# SCH_M5_Stick_RedHat_Shield_2022-06-05.net
KiCad netlist of a schematic drawn in EasyEDA
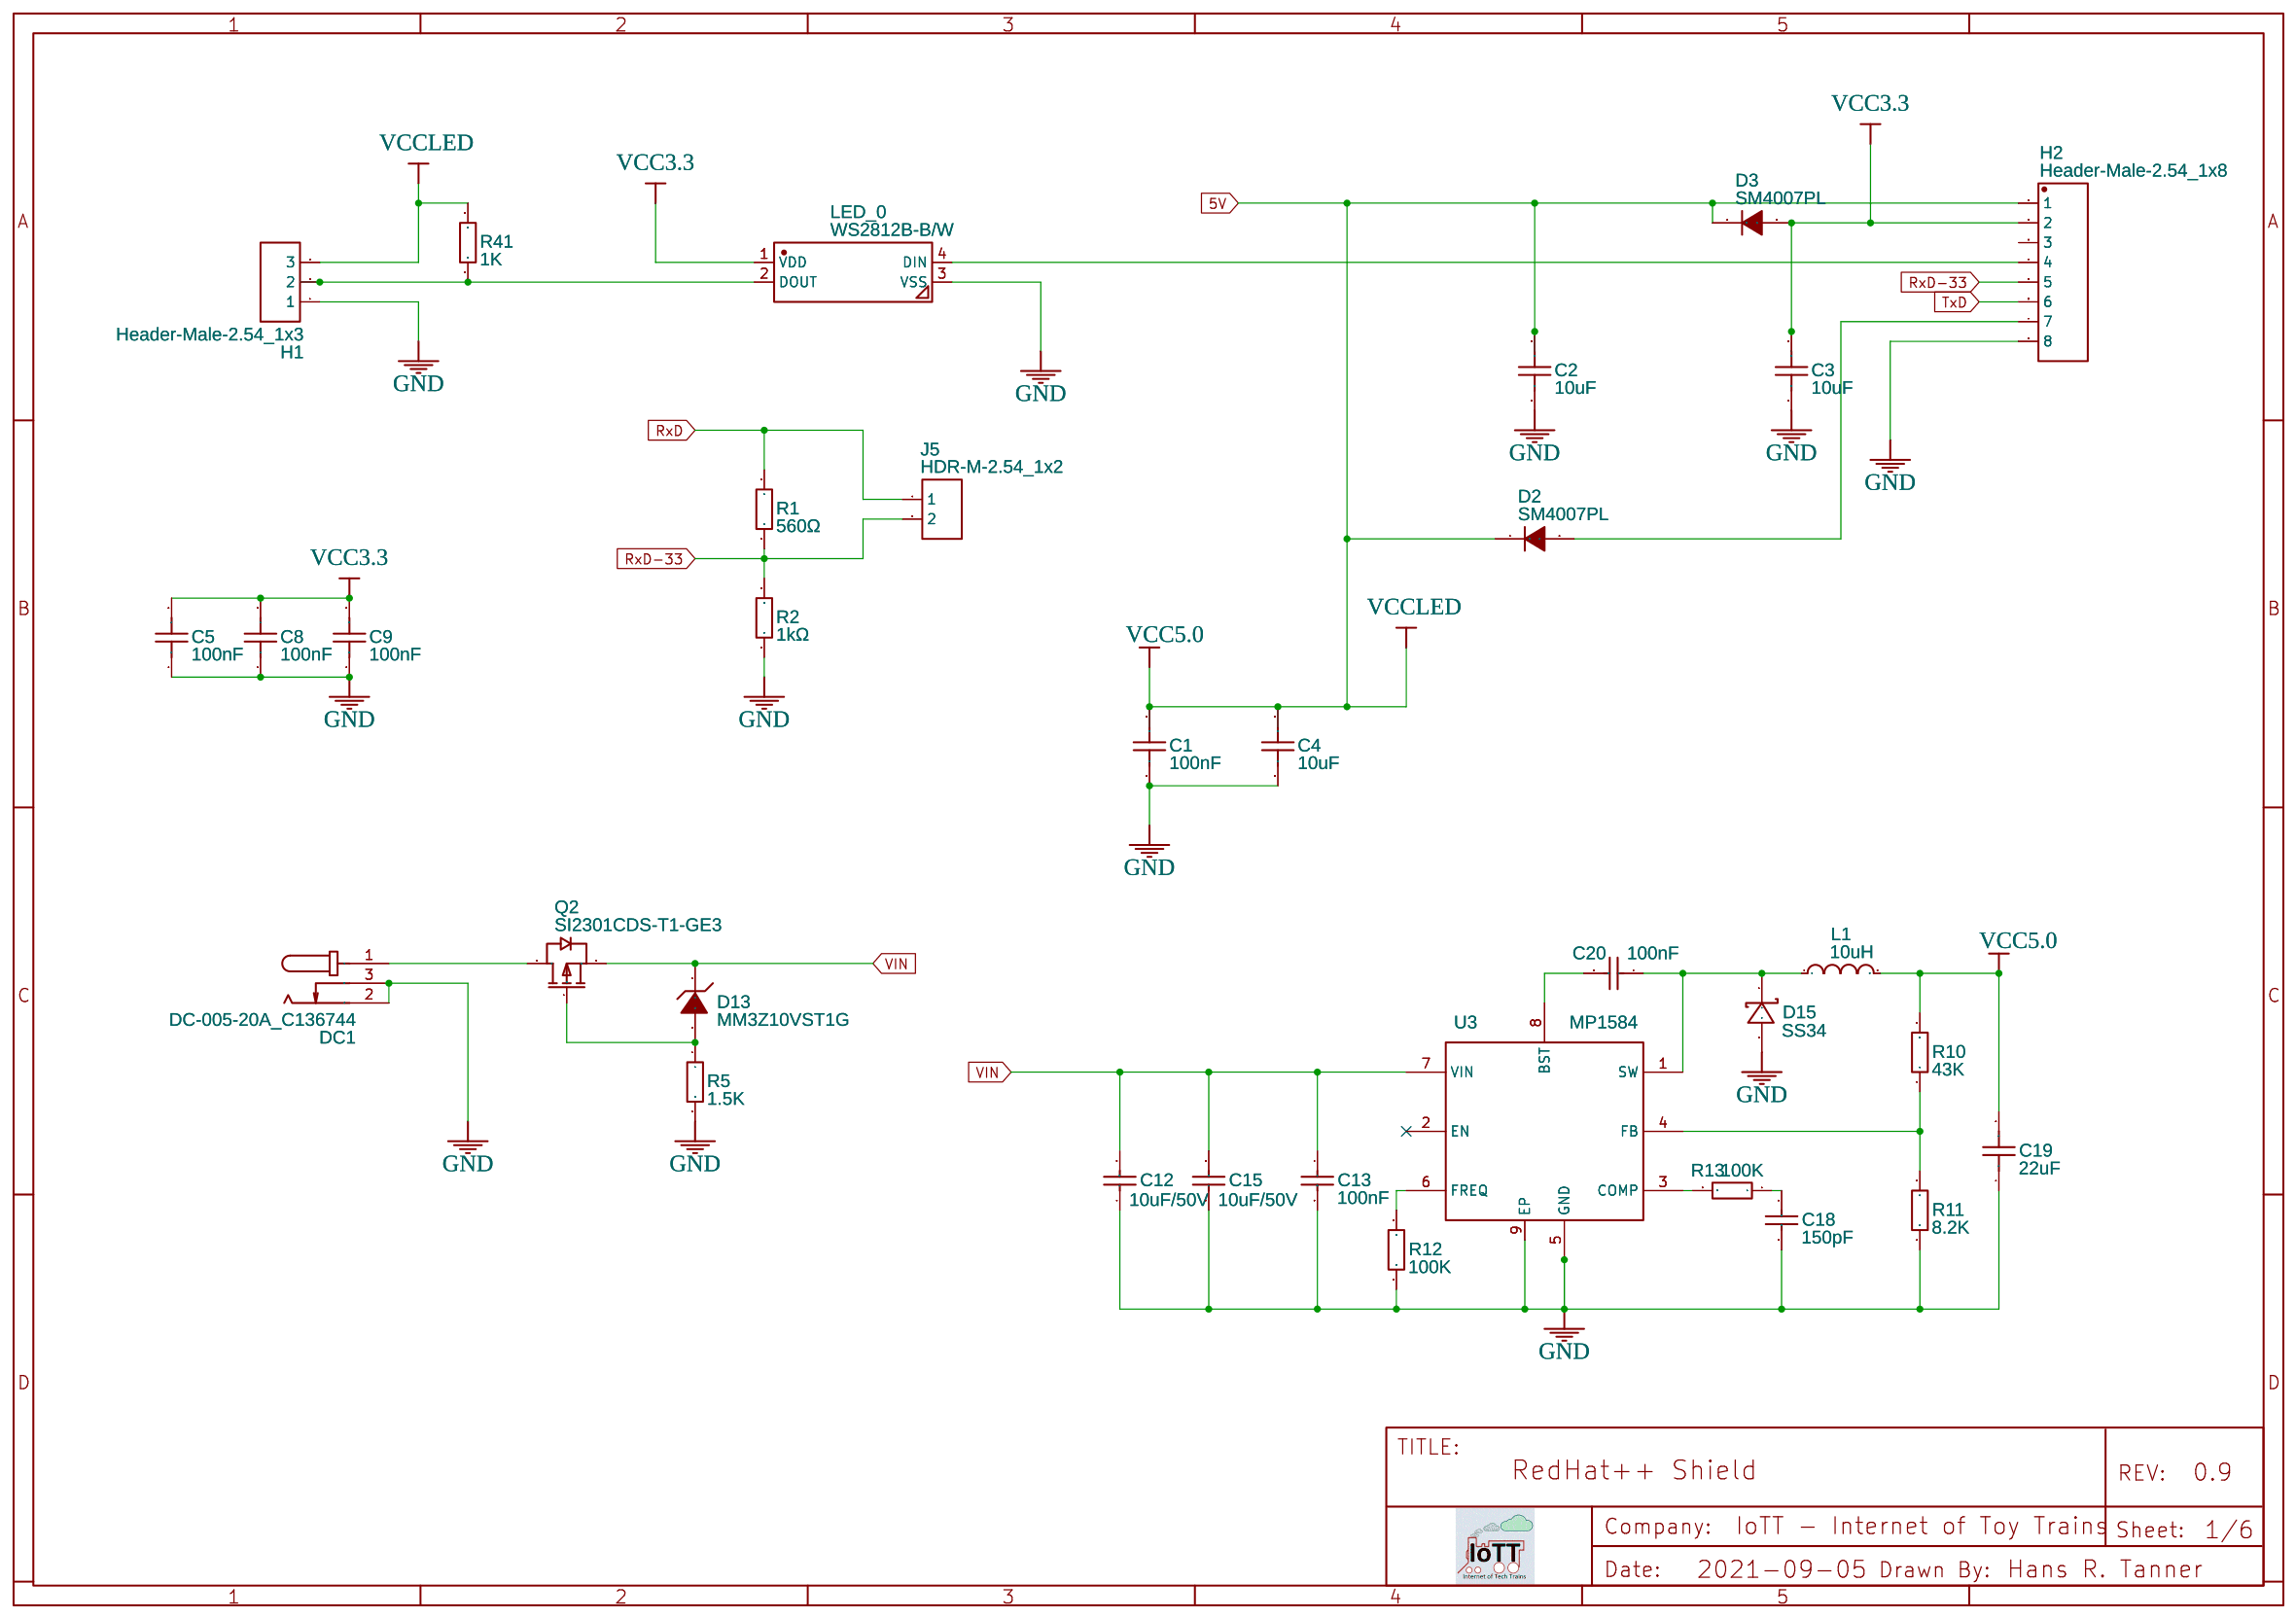
[diagram p0: RedHat++ Shield Main]
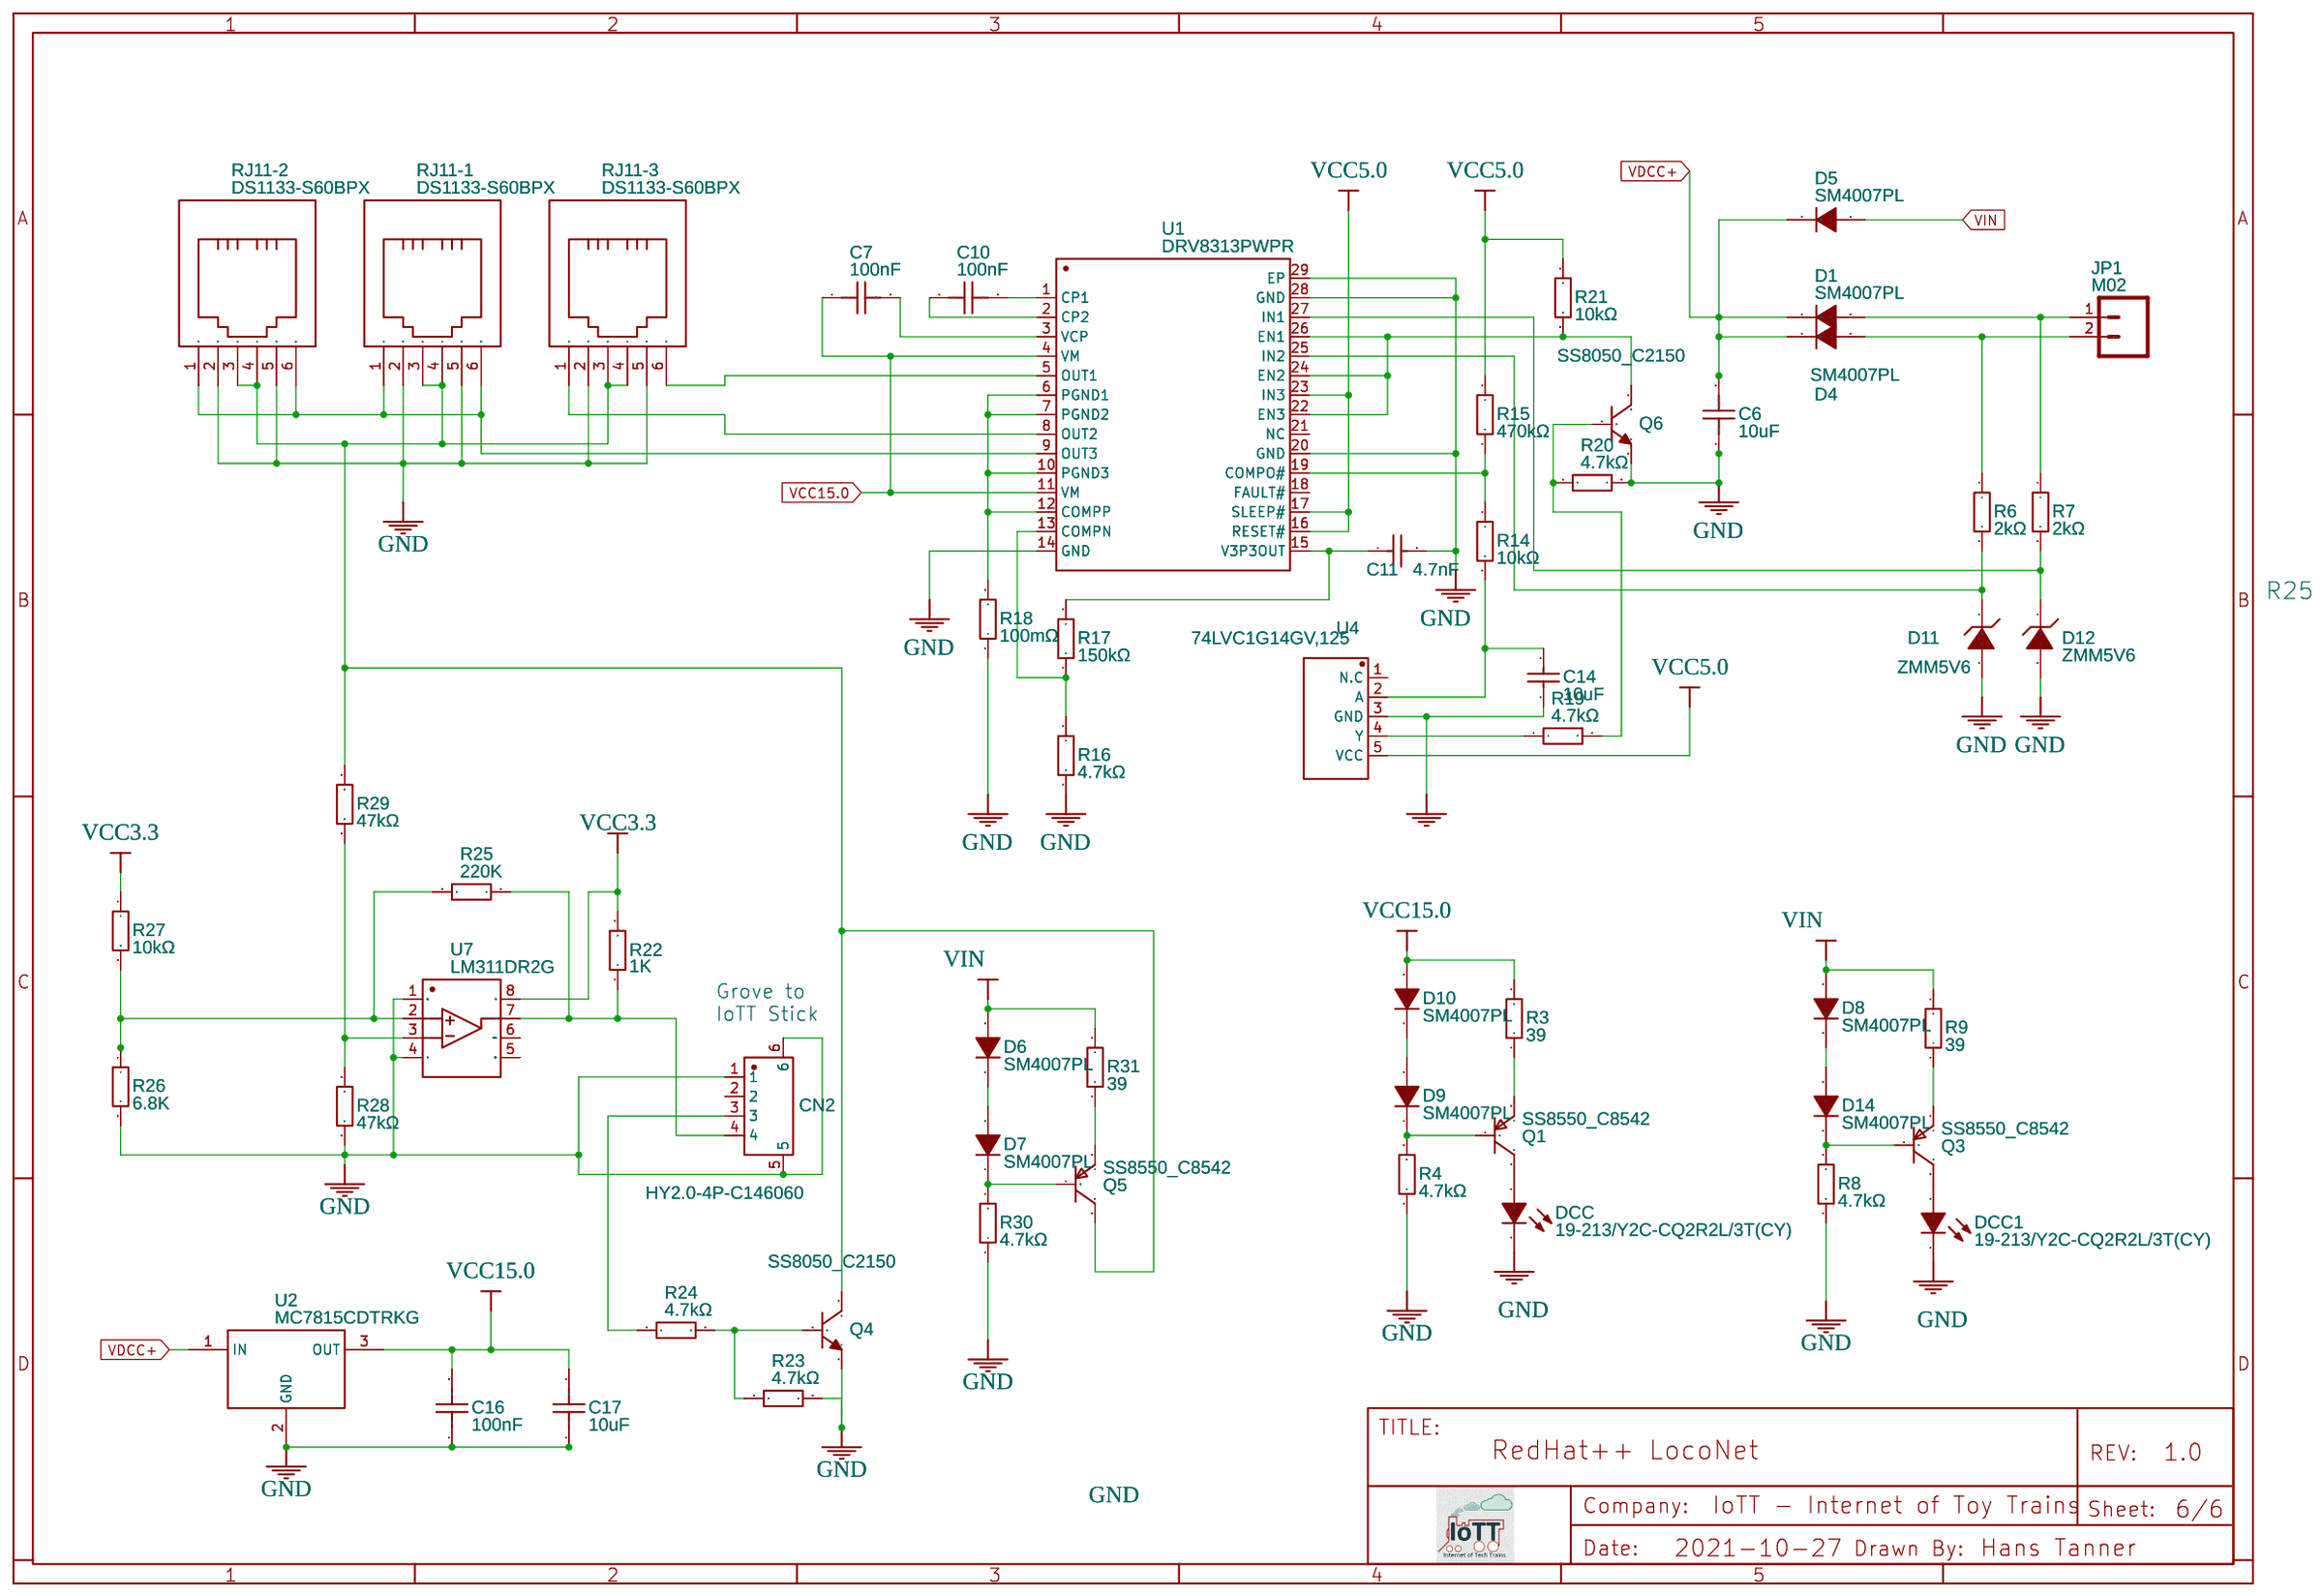
[diagram p1: LocoNet]
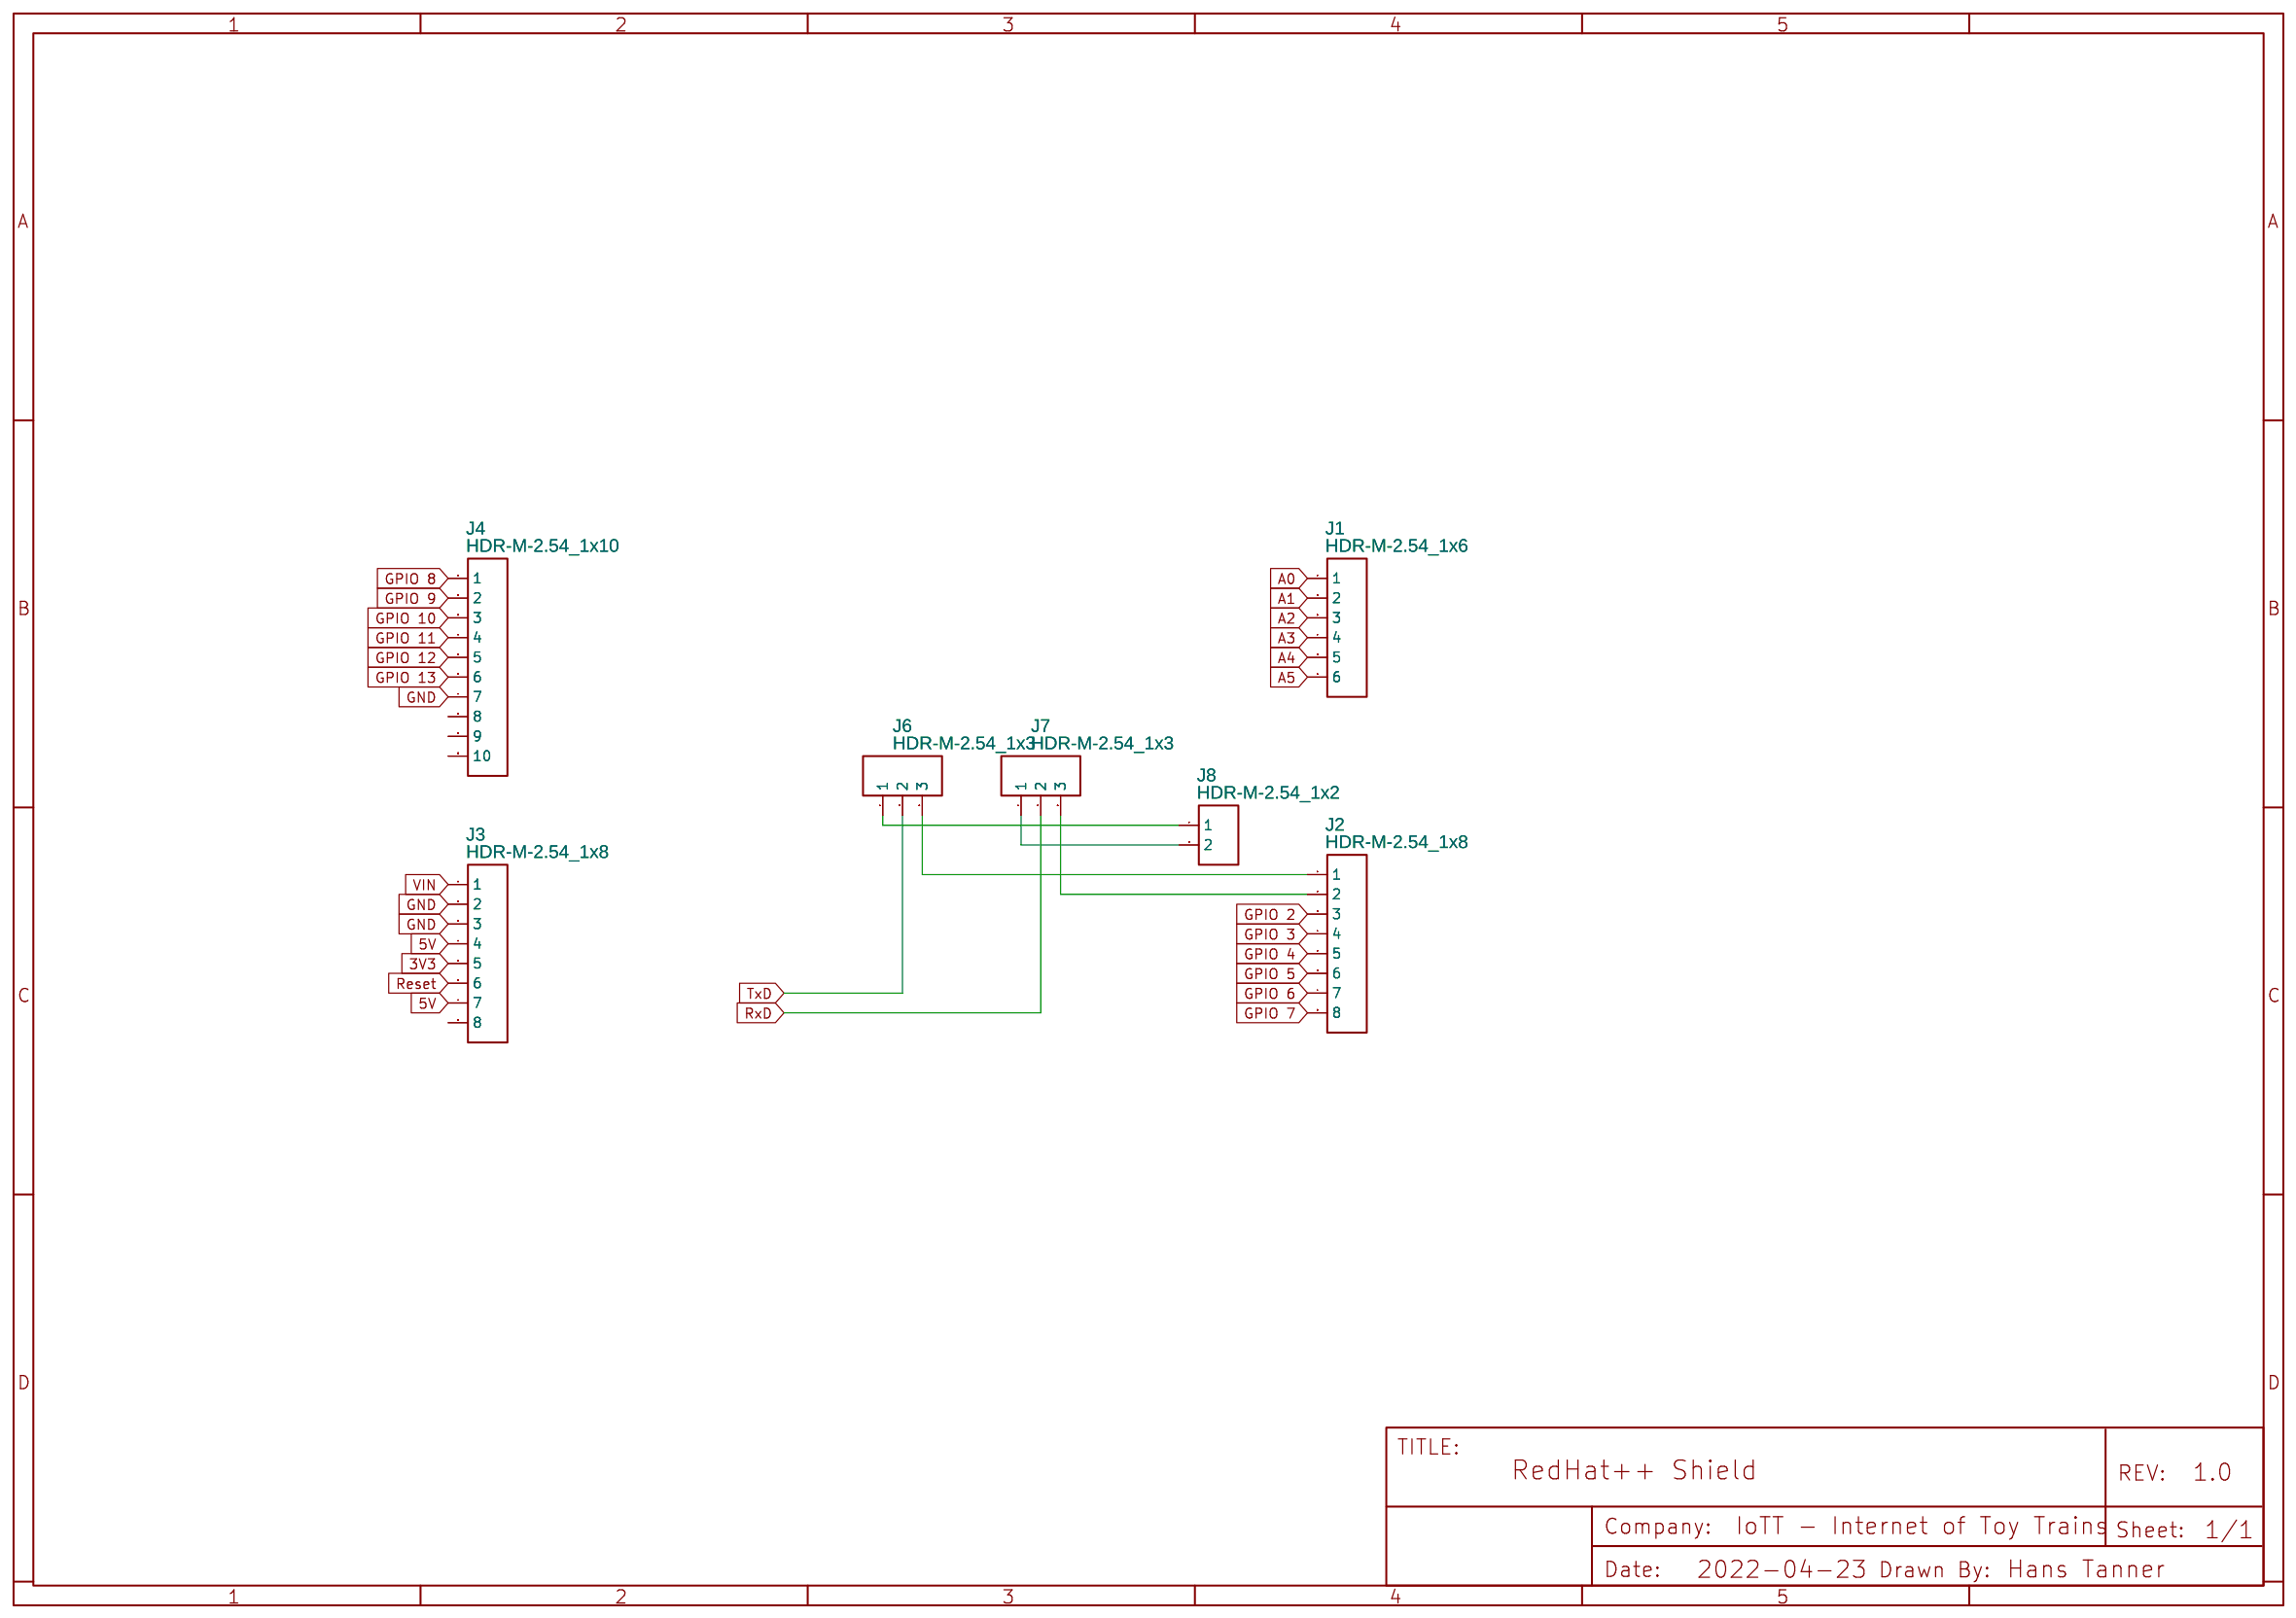
[diagram p2: Arduino Headers]

(export (version "E")
  (design (tool "Eeschema 10.0.6"))
  (components
    (comp (ref "C1")
      (value "100nF")
      (fields
        (field (name "BOM_Manufacturer Part") "CC0603KRX7R9BB104")
        (field (name "BOM_Supplier Part") "C14663")
      )
      (libsource (lib "") (part "CC0603KRX7R9BB104"))
    )
    (comp (ref "C2")
      (value "10uF")
      (fields
        (field (name "BOM_Manufacturer Part") "GRM21BR61H106KE43L")
        (field (name "BOM_Supplier Part") "C440198")
      )
      (libsource (lib "") (part "GRM21BR61H106KE43L"))
    )
    (comp (ref "C3")
      (value "10uF")
      (fields
        (field (name "BOM_Manufacturer Part") "GRM21BR61H106KE43L")
        (field (name "BOM_Supplier Part") "C440198")
      )
      (libsource (lib "") (part "GRM21BR61H106KE43L"))
    )
    (comp (ref "C4")
      (value "10uF")
      (fields
        (field (name "BOM_Manufacturer Part") "GRM21BR61H106KE43L")
        (field (name "BOM_Supplier Part") "C440198")
      )
      (libsource (lib "") (part "GRM21BR61H106KE43L"))
    )
    (comp (ref "C5")
      (value "100nF")
      (fields
        (field (name "BOM_Manufacturer Part") "CC0603KRX7R9BB104")
        (field (name "BOM_Supplier Part") "C14663")
      )
      (libsource (lib "") (part "CC0603KRX7R9BB104"))
    )
    (comp (ref "C8")
      (value "100nF")
      (fields
        (field (name "BOM_Manufacturer Part") "CC0603KRX7R9BB104")
        (field (name "BOM_Supplier Part") "C14663")
      )
      (libsource (lib "") (part "CC0603KRX7R9BB104"))
    )
    (comp (ref "C9")
      (value "100nF")
      (fields
        (field (name "BOM_Manufacturer Part") "CC0603KRX7R9BB104")
        (field (name "BOM_Supplier Part") "C14663")
      )
      (libsource (lib "") (part "CC0603KRX7R9BB104"))
    )
    (comp (ref "C12")
      (value "10uF/50V")
      (fields
        (field (name "BOM_Manufacturer Part") "CL31A106KBHNNNE")
        (field (name "BOM_Supplier Part") "C13585")
      )
      (libsource (lib "") (part "CL31A106KBHNNNE"))
    )
    (comp (ref "C13")
      (value "100nF")
      (fields
        (field (name "BOM_Manufacturer Part") "CL31B104KBCNNNC")
        (field (name "BOM_Supplier Part") "C24497")
      )
      (libsource (lib "") (part "CL31B104KBCNNNC_1"))
    )
    (comp (ref "C15")
      (value "10uF/50V")
      (fields
        (field (name "BOM_Manufacturer Part") "CL31A106KBHNNNE")
        (field (name "BOM_Supplier Part") "C13585")
      )
      (libsource (lib "") (part "CL31A106KBHNNNE"))
    )
    (comp (ref "C18")
      (value "150pF")
      (fields
        (field (name "BOM_Manufacturer Part") "0805B151K500NT")
        (field (name "BOM_Supplier Part") "C1716")
      )
      (libsource (lib "") (part "0805B151K500NT"))
    )
    (comp (ref "C19")
      (value "22uF")
      (fields
        (field (name "BOM_Manufacturer Part") "CL21A226MAQNNNE")
        (field (name "BOM_Supplier Part") "C45783")
      )
      (libsource (lib "") (part "CL21A226MAQNNNE"))
    )
    (comp (ref "C20")
      (value "100nF")
      (fields
        (field (name "BOM_Manufacturer Part") "CL31B104KBCNNNC")
        (field (name "BOM_Supplier Part") "C24497")
      )
      (libsource (lib "") (part "CL31B104KBCNNNC"))
    )
    (comp (ref "D2")
      (value "SM4007PL")
      (fields (field (name "BOM_Supplier Part") "C64898"))
      (libsource (lib "") (part "SM4007PL"))
    )
    (comp (ref "D3")
      (value "SM4007PL")
      (fields (field (name "BOM_Supplier Part") "C64898"))
      (libsource (lib "") (part "SM4007PL"))
    )
    (comp (ref "D13")
      (value "MM3Z10VST1G")
      (fields (field (name "BOM_Supplier Part") "C235983"))
      (libsource (lib "") (part "MM3Z10VST1G"))
    )
    (comp (ref "D15")
      (value "SS34")
      (fields (field (name "BOM_Supplier Part") "C8678"))
      (libsource (lib "") (part "SS34_C8678"))
    )
    (comp (ref "DC1")
      (value "DC-005-20A_C136744")
      (fields
        (field (name "BOM_Manufacturer Part") "DC-005-20A")
        (field (name "BOM_Supplier Part") "C136744")
      )
      (libsource (lib "") (part "DC-005-20A_C136744"))
    )
    (comp (ref "H1")
      (value "Header-Male-2.54_1x3")
      (fields
        (field (name "BOM_Manufacturer Part") "Header2.54mm 1*3P")
        (field (name "BOM_Supplier Part") "C49257")
      )
      (libsource (lib "") (part "Header-Male-2.54_1x3"))
    )
    (comp (ref "H2")
      (value "Header-Male-2.54_1x8")
      (fields
        (field (name "BOM_Manufacturer Part") "210S-1*8P L=11.6MMGold-plated black")
        (field (name "BOM_Supplier Part") "C124381")
      )
      (libsource (lib "") (part "Header-Male-2.54_1x8"))
    )
    (comp (ref "J5")
      (value "HDR-M-2.54_1x2")
      (fields (field (name "BOM_Supplier Part") "C124375"))
      (libsource (lib "") (part "HDR-M-2.54_1x2"))
    )
    (comp (ref "L1")
      (value "10uH")
      (fields
        (field (name "BOM_Manufacturer Part") "MWSA0603-100MT")
        (field (name "BOM_Supplier Part") "C132141")
      )
      (libsource (lib "") (part "MWSA0603-100MT"))
    )
    (comp (ref "LED_0")
      (value "WS2812B-B/W")
      (fields (field (name "BOM_Supplier Part") "C2761795"))
      (libsource (lib "") (part "WS2812B-B/W"))
    )
    (comp (ref "Q2")
      (value "SI2301CDS-T1-GE3")
      (fields (field (name "BOM_Supplier Part") "C10487"))
      (libsource (lib "") (part "SI2301CDS-T1-GE3"))
    )
    (comp (ref "R1")
      (value "560Ω")
      (fields
        (field (name "BOM_Manufacturer Part") "0603WAF5600T5E")
        (field (name "BOM_Supplier Part") "C23204")
      )
      (libsource (lib "") (part "0603WAF5600T5E"))
    )
    (comp (ref "R2")
      (value "1kΩ")
      (fields
        (field (name "BOM_Manufacturer Part") "0402WGF1001TCE")
        (field (name "BOM_Supplier Part") "C11702")
      )
      (libsource (lib "") (part "0402WGF1001TCE"))
    )
    (comp (ref "R5")
      (value "1.5K")
      (fields
        (field (name "BOM_Manufacturer Part") "0402WGF1501TCE")
        (field (name "BOM_Supplier Part") "C25867")
      )
      (libsource (lib "") (part "0402WGF1501TCE"))
    )
    (comp (ref "R10")
      (value "43K")
      (fields
        (field (name "BOM_Manufacturer Part") "0805W8F4302T5E")
        (field (name "BOM_Supplier Part") "C17695")
      )
      (libsource (lib "") (part "0805W8F4302T5E"))
    )
    (comp (ref "R11")
      (value "8.2K")
      (fields
        (field (name "BOM_Manufacturer Part") "0805W8F8201T5E")
        (field (name "BOM_Supplier Part") "C17828")
      )
      (libsource (lib "") (part "0805W8F8201T5E"))
    )
    (comp (ref "R12")
      (value "100K")
      (fields
        (field (name "BOM_Manufacturer Part") "0805W8F1003T5E")
        (field (name "BOM_Supplier Part") "C17407")
      )
      (libsource (lib "") (part "0805W8F1003T5E_1"))
    )
    (comp (ref "R13")
      (value "100K")
      (fields
        (field (name "BOM_Manufacturer Part") "0805W8F1003T5E")
        (field (name "BOM_Supplier Part") "C17407")
      )
      (libsource (lib "") (part "0805W8F1003T5E"))
    )
    (comp (ref "R41")
      (value "1K")
      (fields
        (field (name "BOM_Manufacturer Part") "0402WGF1001TCE")
        (field (name "BOM_Supplier Part") "C11702")
      )
      (libsource (lib "") (part "0402WGF1001TCE"))
    )
    (comp (ref "U3")
      (value "MP1584")
      (fields
        (field (name "BOM_Manufacturer Part") "MP1584EN-LF-Z")
        (field (name "BOM_Supplier Part") "C15051")
      )
      (libsource (lib "") (part "MP1584EN-LF-Z"))
    )
    (comp (ref "C6")
      (value "10uF")
      (fields
        (field (name "BOM_Manufacturer Part") "GRM21BR61H106KE43L")
        (field (name "BOM_Supplier Part") "C440198")
      )
      (libsource (lib "") (part "GRM21BR61H106KE43L"))
    )
    (comp (ref "C7")
      (value "100nF")
      (fields
        (field (name "BOM_Manufacturer Part") "CC0603KRX7R9BB104")
        (field (name "BOM_Supplier Part") "C14663")
      )
      (libsource (lib "") (part "CC0603KRX7R9BB104_1"))
    )
    (comp (ref "C10")
      (value "100nF")
      (fields
        (field (name "BOM_Manufacturer Part") "CC0603KRX7R9BB104")
        (field (name "BOM_Supplier Part") "C14663")
      )
      (libsource (lib "") (part "CC0603KRX7R9BB104_1"))
    )
    (comp (ref "C11")
      (value "4.7nF")
      (fields
        (field (name "BOM_Manufacturer Part") "0402B472K500NT")
        (field (name "BOM_Supplier Part") "C1538")
      )
      (libsource (lib "") (part "0402B472K500NT"))
    )
    (comp (ref "C14")
      (value "10uF")
      (fields
        (field (name "BOM_Manufacturer Part") "CL21A106KAYNNNE")
        (field (name "BOM_Supplier Part") "C15850")
      )
      (libsource (lib "") (part "CL21A106KAYNNNE"))
    )
    (comp (ref "C16")
      (value "100nF")
      (fields
        (field (name "BOM_Manufacturer Part") "CC0603KRX7R9BB104")
        (field (name "BOM_Supplier Part") "C14663")
      )
      (libsource (lib "") (part "CC0603KRX7R9BB104"))
    )
    (comp (ref "C17")
      (value "10uF")
      (fields
        (field (name "BOM_Manufacturer Part") "GRM21BR61H106KE43L")
        (field (name "BOM_Supplier Part") "C440198")
      )
      (libsource (lib "") (part "GRM21BR61H106KE43L"))
    )
    (comp (ref "CN2")
      (value "HY2.0-4P-C146060")
      (fields (field (name "BOM_Supplier Part") "C146060"))
      (libsource (lib "") (part "HY2.0-4P-C146060"))
    )
    (comp (ref "D1")
      (value "SM4007PL")
      (fields (field (name "BOM_Supplier Part") "C64898"))
      (libsource (lib "") (part "SM4007PL_1"))
    )
    (comp (ref "D4")
      (value "SM4007PL")
      (fields (field (name "BOM_Supplier Part") "C64898"))
      (libsource (lib "") (part "SM4007PL_1"))
    )
    (comp (ref "D5")
      (value "SM4007PL")
      (fields (field (name "BOM_Supplier Part") "C64898"))
      (libsource (lib "") (part "SM4007PL_1"))
    )
    (comp (ref "D6")
      (value "SM4007PL")
      (fields (field (name "BOM_Supplier Part") "C64898"))
      (libsource (lib "") (part "SM4007PL"))
    )
    (comp (ref "D7")
      (value "SM4007PL")
      (fields (field (name "BOM_Supplier Part") "C64898"))
      (libsource (lib "") (part "SM4007PL"))
    )
    (comp (ref "D8")
      (value "SM4007PL")
      (fields (field (name "BOM_Supplier Part") "C64898"))
      (libsource (lib "") (part "SM4007PL"))
    )
    (comp (ref "D9")
      (value "SM4007PL")
      (fields (field (name "BOM_Supplier Part") "C64898"))
      (libsource (lib "") (part "SM4007PL"))
    )
    (comp (ref "D10")
      (value "SM4007PL")
      (fields (field (name "BOM_Supplier Part") "C64898"))
      (libsource (lib "") (part "SM4007PL"))
    )
    (comp (ref "D11")
      (value "ZMM5V6")
      (fields (field (name "BOM_Supplier Part") "C8062"))
      (libsource (lib "") (part "ZMM5V6"))
    )
    (comp (ref "D12")
      (value "ZMM5V6")
      (fields (field (name "BOM_Supplier Part") "C8062"))
      (libsource (lib "") (part "ZMM5V6"))
    )
    (comp (ref "D14")
      (value "SM4007PL")
      (fields (field (name "BOM_Supplier Part") "C64898"))
      (libsource (lib "") (part "SM4007PL"))
    )
    (comp (ref "DCC")
      (value "19-213/Y2C-CQ2R2L/3T(CY)")
      (fields (field (name "BOM_Supplier Part") "C72038"))
      (libsource (lib "") (part "19-213/Y2C-CQ2R2L/3T(CY)"))
    )
    (comp (ref "DCC1")
      (value "19-213/Y2C-CQ2R2L/3T(CY)")
      (fields (field (name "BOM_Supplier Part") "C72038"))
      (libsource (lib "") (part "19-213/Y2C-CQ2R2L/3T(CY)"))
    )
    (comp (ref "JP1") (value "M02") (libsource (lib "") (part "M02")))
    (comp (ref "Q1")
      (value "SS8550_C8542")
      (fields (field (name "BOM_Manufacturer Part") "SS8550") (field (name "BOM_Supplier Part") "C8542"))
      (libsource (lib "") (part "SS8550_C8542"))
    )
    (comp (ref "Q3")
      (value "SS8550_C8542")
      (fields (field (name "BOM_Manufacturer Part") "SS8550") (field (name "BOM_Supplier Part") "C8542"))
      (libsource (lib "") (part "SS8550_C8542"))
    )
    (comp (ref "Q4")
      (value "SS8050_C2150")
      (fields (field (name "BOM_Manufacturer Part") "SS8050") (field (name "BOM_Supplier Part") "C2150"))
      (libsource (lib "") (part "SS8050_C2150"))
    )
    (comp (ref "Q5")
      (value "SS8550_C8542")
      (fields (field (name "BOM_Manufacturer Part") "SS8550") (field (name "BOM_Supplier Part") "C8542"))
      (libsource (lib "") (part "SS8550_C8542"))
    )
    (comp (ref "Q6")
      (value "SS8050_C2150")
      (fields (field (name "BOM_Manufacturer Part") "SS8050") (field (name "BOM_Supplier Part") "C2150"))
      (libsource (lib "") (part "SS8050_C2150"))
    )
    (comp (ref "R3")
      (value "39")
      (fields
        (field (name "BOM_Manufacturer Part") "TC0325B390JT5E")
        (field (name "BOM_Supplier Part") "C146566")
      )
      (libsource (lib "") (part "TC0325B390JT5E"))
    )
    (comp (ref "R4")
      (value "4.7kΩ")
      (fields
        (field (name "BOM_Manufacturer Part") "0402WGF4701TCE")
        (field (name "BOM_Supplier Part") "C25900")
      )
      (libsource (lib "") (part "0402WGF4701TCE"))
    )
    (comp (ref "R6")
      (value "2kΩ")
      (fields
        (field (name "BOM_Manufacturer Part") "0402WGF2001TCE")
        (field (name "BOM_Supplier Part") "C4109")
      )
      (libsource (lib "") (part "0402WGF2001TCE"))
    )
    (comp (ref "R7")
      (value "2kΩ")
      (fields
        (field (name "BOM_Manufacturer Part") "0402WGF2001TCE")
        (field (name "BOM_Supplier Part") "C4109")
      )
      (libsource (lib "") (part "0402WGF2001TCE"))
    )
    (comp (ref "R8")
      (value "4.7kΩ")
      (fields
        (field (name "BOM_Manufacturer Part") "0402WGF4701TCE")
        (field (name "BOM_Supplier Part") "C25900")
      )
      (libsource (lib "") (part "0402WGF4701TCE"))
    )
    (comp (ref "R9")
      (value "39")
      (fields
        (field (name "BOM_Manufacturer Part") "TC0325B390JT5E")
        (field (name "BOM_Supplier Part") "C146566")
      )
      (libsource (lib "") (part "TC0325B390JT5E"))
    )
    (comp (ref "R14")
      (value "10kΩ")
      (fields
        (field (name "BOM_Manufacturer Part") "0402WGF1002TCE")
        (field (name "BOM_Supplier Part") "C25744")
      )
      (libsource (lib "") (part "0402WGF1002TCE"))
    )
    (comp (ref "R15")
      (value "470kΩ")
      (fields
        (field (name "BOM_Manufacturer Part") "0603WAF4703T5E")
        (field (name "BOM_Supplier Part") "C23178")
      )
      (libsource (lib "") (part "0603WAF4703T5E"))
    )
    (comp (ref "R16")
      (value "4.7kΩ")
      (fields
        (field (name "BOM_Manufacturer Part") "0402WGF4701TCE")
        (field (name "BOM_Supplier Part") "C25900")
      )
      (libsource (lib "") (part "0402WGF4701TCE"))
    )
    (comp (ref "R17")
      (value "150kΩ")
      (fields
        (field (name "BOM_Manufacturer Part") "0603WAF1503T5E")
        (field (name "BOM_Supplier Part") "C22807")
      )
      (libsource (lib "") (part "0603WAF1503T5E"))
    )
    (comp (ref "R18")
      (value "100mΩ")
      (fields
        (field (name "BOM_Manufacturer Part") "1206W4F100LT5E")
        (field (name "BOM_Supplier Part") "C25334")
      )
      (libsource (lib "") (part "1206W4F100LT5E"))
    )
    (comp (ref "R19")
      (value "4.7kΩ")
      (fields
        (field (name "BOM_Manufacturer Part") "0402WGF4701TCE")
        (field (name "BOM_Supplier Part") "C25900")
      )
      (libsource (lib "") (part "0402WGF4701TCE_1"))
    )
    (comp (ref "R20")
      (value "4.7kΩ")
      (fields
        (field (name "BOM_Manufacturer Part") "0402WGF4701TCE")
        (field (name "BOM_Supplier Part") "C25900")
      )
      (libsource (lib "") (part "0402WGF4701TCE_1"))
    )
    (comp (ref "R21")
      (value "10kΩ")
      (fields
        (field (name "BOM_Manufacturer Part") "0402WGF1002TCE")
        (field (name "BOM_Supplier Part") "C25744")
      )
      (libsource (lib "") (part "0402WGF1002TCE"))
    )
    (comp (ref "R22")
      (value "1K")
      (fields
        (field (name "BOM_Manufacturer Part") "0402WGF1001TCE")
        (field (name "BOM_Supplier Part") "C11702")
      )
      (libsource (lib "") (part "0402WGF1001TCE"))
    )
    (comp (ref "R23")
      (value "4.7kΩ")
      (fields
        (field (name "BOM_Manufacturer Part") "0402WGF4701TCE")
        (field (name "BOM_Supplier Part") "C25900")
      )
      (libsource (lib "") (part "0402WGF4701TCE_1"))
    )
    (comp (ref "R24")
      (value "4.7kΩ")
      (fields
        (field (name "BOM_Manufacturer Part") "0402WGF4701TCE")
        (field (name "BOM_Supplier Part") "C25900")
      )
      (libsource (lib "") (part "0402WGF4701TCE_1"))
    )
    (comp (ref "R25")
      (value "220K")
      (fields
        (field (name "BOM_Manufacturer Part") "0603WAF2203T5E")
        (field (name "BOM_Supplier Part") "C22961")
      )
      (libsource (lib "") (part "0603WAF2203T5E"))
    )
    (comp (ref "R26")
      (value "6.8K")
      (fields
        (field (name "BOM_Manufacturer Part") "0603WAF6801T5E")
        (field (name "BOM_Supplier Part") "C23212")
      )
      (libsource (lib "") (part "0603WAF6801T5E"))
    )
    (comp (ref "R27")
      (value "10kΩ")
      (fields
        (field (name "BOM_Manufacturer Part") "0402WGF1002TCE")
        (field (name "BOM_Supplier Part") "C25744")
      )
      (libsource (lib "") (part "0402WGF1002TCE"))
    )
    (comp (ref "R28")
      (value "47kΩ")
      (fields
        (field (name "BOM_Manufacturer Part") "0402WGF4702TCE")
        (field (name "BOM_Supplier Part") "C25792")
      )
      (libsource (lib "") (part "0402WGF4702TCE"))
    )
    (comp (ref "R29")
      (value "47kΩ")
      (fields
        (field (name "BOM_Manufacturer Part") "0402WGF4702TCE")
        (field (name "BOM_Supplier Part") "C25792")
      )
      (libsource (lib "") (part "0402WGF4702TCE"))
    )
    (comp (ref "R30")
      (value "4.7kΩ")
      (fields
        (field (name "BOM_Manufacturer Part") "0402WGF4701TCE")
        (field (name "BOM_Supplier Part") "C25900")
      )
      (libsource (lib "") (part "0402WGF4701TCE"))
    )
    (comp (ref "R31")
      (value "39")
      (fields
        (field (name "BOM_Manufacturer Part") "TC0325B390JT5E")
        (field (name "BOM_Supplier Part") "C146566")
      )
      (libsource (lib "") (part "TC0325B390JT5E"))
    )
    (comp (ref "RJ11-1")
      (value "DS1133-S60BPX")
      (fields (field (name "BOM_Supplier Part") "C77859"))
      (libsource (lib "") (part "Unknown_215_-660"))
    )
    (comp (ref "RJ11-2")
      (value "DS1133-S60BPX")
      (fields (field (name "BOM_Supplier Part") "C77859"))
      (libsource (lib "") (part "Unknown_120_-660"))
    )
    (comp (ref "RJ11-3")
      (value "DS1133-S60BPX")
      (fields (field (name "BOM_Supplier Part") "C77859"))
      (libsource (lib "") (part "Unknown_310_-660"))
    )
    (comp (ref "U1")
      (value "DRV8313PWPR")
      (fields (field (name "BOM_Supplier Part") "C92482"))
      (libsource (lib "") (part "DRV8313PWPR"))
    )
    (comp (ref "U2")
      (value "MC7815CDTRKG")
      (fields (field (name "BOM_Supplier Part") "C133887"))
      (libsource (lib "") (part "MC7815CDTRKG"))
    )
    (comp (ref "U4")
      (value "74LVC1G14GV,125")
      (fields (field (name "BOM_Supplier Part") "C131093"))
      (libsource (lib "") (part "74LVC1G14GV,125"))
    )
    (comp (ref "U7")
      (value "LM311DR2G")
      (fields (field (name "BOM_Supplier Part") "C231850"))
      (libsource (lib "") (part "LM311DR2G"))
    )
    (comp (ref "J1")
      (value "HDR-M-2.54_1x6")
      (fields (field (name "BOM_Supplier Part") "C190819"))
      (libsource (lib "") (part "HDR-M-2.54_1x6"))
    )
    (comp (ref "J2")
      (value "HDR-M-2.54_1x8")
      (fields (field (name "BOM_Supplier Part") "C190820"))
      (libsource (lib "") (part "HDR-M-2.54_1x8"))
    )
    (comp (ref "J3")
      (value "HDR-M-2.54_1x8")
      (fields (field (name "BOM_Supplier Part") "C190820"))
      (libsource (lib "") (part "HDR-M-2.54_1x8"))
    )
    (comp (ref "J4")
      (value "HDR-M-2.54_1x10")
      (fields (field (name "BOM_Supplier Part") "C57369"))
      (libsource (lib "") (part "HDR-M-2.54_1x10"))
    )
    (comp (ref "J6")
      (value "HDR-M-2.54_1x3")
      (fields (field (name "BOM_Supplier Part") "C180248"))
      (libsource (lib "") (part "HDR-M-2.54_1x3"))
    )
    (comp (ref "J7")
      (value "HDR-M-2.54_1x3")
      (fields (field (name "BOM_Supplier Part") "C180248"))
      (libsource (lib "") (part "HDR-M-2.54_1x3"))
    )
    (comp (ref "J8")
      (value "HDR-M-2.54_1x2")
      (fields (field (name "BOM_Supplier Part") "C124375"))
      (libsource (lib "") (part "HDR-M-2.54_1x2"))
    )
  )
  (nets
    (net (code "1") (name "3V3") (class "Default")
      (node (ref "J3") (pin "5") (pinfunction "5_5") (pintype "unspecified"))
    )
    (net (code "2") (name "5V") (class "Default")
      (node (ref "C1") (pin "2") (pinfunction "2_2") (pintype "unspecified"))
      (node (ref "C19") (pin "2") (pinfunction "2_2") (pintype "unspecified"))
      (node (ref "C2") (pin "2") (pinfunction "2_2") (pintype "unspecified"))
      (node (ref "C4") (pin "2") (pinfunction "2_2") (pintype "unspecified"))
      (node (ref "D2") (pin "1") (pinfunction "C_1") (pintype "unspecified"))
      (node (ref "D3") (pin "1") (pinfunction "C_1") (pintype "unspecified"))
      (node (ref "H1") (pin "3") (pinfunction "3_3") (pintype "input"))
      (node (ref "H2") (pin "1") (pinfunction "1_1") (pintype "unspecified"))
      (node (ref "J3") (pin "4") (pinfunction "4_4") (pintype "unspecified"))
      (node (ref "J3") (pin "7") (pinfunction "7_7") (pintype "unspecified"))
      (node (ref "L1") (pin "2") (pinfunction "2_2") (pintype "unspecified"))
      (node (ref "R10") (pin "2") (pinfunction "2_2") (pintype "input"))
      (node (ref "R15") (pin "1") (pinfunction "1_1") (pintype "input"))
      (node (ref "R21") (pin "1") (pinfunction "1_1") (pintype "input"))
      (node (ref "R41") (pin "2") (pinfunction "2_2") (pintype "input"))
      (node (ref "U1") (pin "16") (pinfunction "RESET#_16") (pintype "unspecified"))
      (node (ref "U1") (pin "17") (pinfunction "SLEEP#_17") (pintype "unspecified"))
      (node (ref "U1") (pin "23") (pinfunction "IN3_23") (pintype "unspecified"))
      (node (ref "U4") (pin "5") (pinfunction "VCC_5") (pintype "unspecified"))
    )
    (net (code "3") (name "A0") (class "Default")
      (node (ref "J1") (pin "1") (pinfunction "1_1") (pintype "input"))
    )
    (net (code "4") (name "A1") (class "Default")
      (node (ref "J1") (pin "2") (pinfunction "2_2") (pintype "input"))
    )
    (net (code "5") (name "A2") (class "Default")
      (node (ref "J1") (pin "3") (pinfunction "3_3") (pintype "input"))
    )
    (net (code "6") (name "A3") (class "Default")
      (node (ref "J1") (pin "4") (pinfunction "4_4") (pintype "input"))
    )
    (net (code "7") (name "A4") (class "Default")
      (node (ref "J1") (pin "5") (pinfunction "5_5") (pintype "input"))
    )
    (net (code "8") (name "A5") (class "Default")
      (node (ref "J1") (pin "6") (pinfunction "6_6") (pintype "input"))
    )
    (net (code "9") (name "GND") (class "Default")
      (node (ref "C1") (pin "1") (pinfunction "1_1") (pintype "unspecified"))
      (node (ref "C11") (pin "2") (pinfunction "2_2") (pintype "input"))
      (node (ref "C12") (pin "1") (pinfunction "1_1") (pintype "input"))
      (node (ref "C13") (pin "2") (pinfunction "2_2") (pintype "input"))
      (node (ref "C14") (pin "1") (pinfunction "1_1") (pintype "input"))
      (node (ref "C15") (pin "1") (pinfunction "1_1") (pintype "input"))
      (node (ref "C16") (pin "1") (pinfunction "1_1") (pintype "unspecified"))
      (node (ref "C17") (pin "1") (pinfunction "1_1") (pintype "unspecified"))
      (node (ref "C18") (pin "1") (pinfunction "1_1") (pintype "input"))
      (node (ref "C19") (pin "1") (pinfunction "1_1") (pintype "unspecified"))
      (node (ref "C2") (pin "1") (pinfunction "1_1") (pintype "unspecified"))
      (node (ref "C3") (pin "1") (pinfunction "1_1") (pintype "unspecified"))
      (node (ref "C4") (pin "1") (pinfunction "1_1") (pintype "unspecified"))
      (node (ref "C5") (pin "1") (pinfunction "1_1") (pintype "unspecified"))
      (node (ref "C6") (pin "1") (pinfunction "1_1") (pintype "unspecified"))
      (node (ref "C8") (pin "1") (pinfunction "1_1") (pintype "unspecified"))
      (node (ref "C9") (pin "1") (pinfunction "1_1") (pintype "unspecified"))
      (node (ref "CN2") (pin "1") (pinfunction "1_1") (pintype "unspecified"))
      (node (ref "CN2") (pin "5") (pinfunction "5_5") (pintype "unspecified"))
      (node (ref "CN2") (pin "6") (pinfunction "6_6") (pintype "unspecified"))
      (node (ref "D11") (pin "2") (pinfunction "A_2") (pintype "unspecified"))
      (node (ref "D12") (pin "2") (pinfunction "A_2") (pintype "unspecified"))
      (node (ref "D15") (pin "2") (pinfunction "A_2") (pintype "unspecified"))
      (node (ref "DC1") (pin "2") (pinfunction "2_2") (pintype "unspecified"))
      (node (ref "DC1") (pin "3") (pinfunction "3_3") (pintype "unspecified"))
      (node (ref "DCC") (pin "2") (pinfunction "C_2") (pintype "input"))
      (node (ref "DCC1") (pin "2") (pinfunction "C_2") (pintype "input"))
      (node (ref "H1") (pin "1") (pinfunction "1_1") (pintype "input"))
      (node (ref "H2") (pin "8") (pinfunction "8_8") (pintype "unspecified"))
      (node (ref "J3") (pin "2") (pinfunction "2_2") (pintype "unspecified"))
      (node (ref "J3") (pin "3") (pinfunction "3_3") (pintype "unspecified"))
      (node (ref "J4") (pin "7") (pinfunction "7_7") (pintype "unspecified"))
      (node (ref "LED_0") (pin "3") (pinfunction "VSS_3") (pintype "unspecified"))
      (node (ref "Q4") (pin "2") (pinfunction "E_2") (pintype "unspecified"))
      (node (ref "Q6") (pin "2") (pinfunction "E_2") (pintype "unspecified"))
      (node (ref "R11") (pin "1") (pinfunction "1_1") (pintype "input"))
      (node (ref "R12") (pin "2") (pinfunction "2_2") (pintype "input"))
      (node (ref "R16") (pin "1") (pinfunction "1_1") (pintype "input"))
      (node (ref "R18") (pin "1") (pinfunction "1_1") (pintype "input"))
      (node (ref "R2") (pin "1") (pinfunction "1_1") (pintype "input"))
      (node (ref "R20") (pin "2") (pinfunction "2_2") (pintype "input"))
      (node (ref "R23") (pin "2") (pinfunction "2_2") (pintype "input"))
      (node (ref "R26") (pin "2") (pinfunction "2_2") (pintype "input"))
      (node (ref "R28") (pin "2") (pinfunction "2_2") (pintype "input"))
      (node (ref "R30") (pin "1") (pinfunction "1_1") (pintype "input"))
      (node (ref "R4") (pin "1") (pinfunction "1_1") (pintype "input"))
      (node (ref "R5") (pin "2") (pinfunction "2_2") (pintype "input"))
      (node (ref "R8") (pin "1") (pinfunction "1_1") (pintype "input"))
      (node (ref "RJ11-1") (pin "2") (pinfunction "2_2") (pintype "unspecified"))
      (node (ref "RJ11-1") (pin "5") (pinfunction "5_5") (pintype "unspecified"))
      (node (ref "RJ11-2") (pin "2") (pinfunction "2_2") (pintype "unspecified"))
      (node (ref "RJ11-2") (pin "5") (pinfunction "5_5") (pintype "unspecified"))
      (node (ref "RJ11-3") (pin "2") (pinfunction "2_2") (pintype "unspecified"))
      (node (ref "RJ11-3") (pin "5") (pinfunction "5_5") (pintype "unspecified"))
      (node (ref "U1") (pin "14") (pinfunction "GND_14") (pintype "unspecified"))
      (node (ref "U1") (pin "20") (pinfunction "GND_20") (pintype "unspecified"))
      (node (ref "U1") (pin "28") (pinfunction "GND_28") (pintype "unspecified"))
      (node (ref "U1") (pin "29") (pinfunction "EP_29") (pintype "unspecified"))
      (node (ref "U2") (pin "2") (pinfunction "GND_2") (pintype "unspecified"))
      (node (ref "U3") (pin "5") (pinfunction "GND_5") (pintype "unspecified"))
      (node (ref "U3") (pin "9") (pinfunction "EP_9") (pintype "unspecified"))
      (node (ref "U4") (pin "3") (pinfunction "GND_3") (pintype "unspecified"))
      (node (ref "U7") (pin "1") (pinfunction "GND_1") (pintype "unspecified"))
      (node (ref "U7") (pin "4") (pinfunction "VEE_4") (pintype "unspecified"))
    )
    (net (code "10") (name "GPIO 2") (class "Default")
      (node (ref "J2") (pin "3") (pinfunction "3_3") (pintype "unspecified"))
    )
    (net (code "11") (name "GPIO 3") (class "Default")
      (node (ref "J2") (pin "4") (pinfunction "4_4") (pintype "unspecified"))
    )
    (net (code "12") (name "GPIO 4") (class "Default")
      (node (ref "J2") (pin "5") (pinfunction "5_5") (pintype "unspecified"))
    )
    (net (code "13") (name "GPIO 5") (class "Default")
      (node (ref "J2") (pin "6") (pinfunction "6_6") (pintype "unspecified"))
    )
    (net (code "14") (name "GPIO 6") (class "Default")
      (node (ref "J2") (pin "7") (pinfunction "7_7") (pintype "unspecified"))
    )
    (net (code "15") (name "GPIO 7") (class "Default")
      (node (ref "J2") (pin "8") (pinfunction "8_8") (pintype "unspecified"))
    )
    (net (code "16") (name "GPIO 8") (class "Default")
      (node (ref "J4") (pin "1") (pinfunction "1_1") (pintype "unspecified"))
    )
    (net (code "17") (name "GPIO 9") (class "Default")
      (node (ref "J4") (pin "2") (pinfunction "2_2") (pintype "unspecified"))
    )
    (net (code "18") (name "GPIO 10") (class "Default")
      (node (ref "J4") (pin "3") (pinfunction "3_3") (pintype "unspecified"))
    )
    (net (code "19") (name "GPIO 11") (class "Default")
      (node (ref "J4") (pin "4") (pinfunction "4_4") (pintype "unspecified"))
    )
    (net (code "20") (name "GPIO 12") (class "Default")
      (node (ref "J4") (pin "5") (pinfunction "5_5") (pintype "unspecified"))
    )
    (net (code "21") (name "GPIO 13") (class "Default")
      (node (ref "J4") (pin "6") (pinfunction "6_6") (pintype "unspecified"))
    )
    (net (code "22") (name "Net-(C18-Pad2)") (class "Default")
      (node (ref "C18") (pin "2") (pinfunction "2_2") (pintype "input"))
      (node (ref "R13") (pin "1") (pinfunction "1_1") (pintype "input"))
    )
    (net (code "23") (name "Net-(CN2-Pad3)") (class "Default")
      (node (ref "CN2") (pin "3") (pinfunction "3_3") (pintype "unspecified"))
      (node (ref "R24") (pin "1") (pinfunction "1_1") (pintype "input"))
    )
    (net (code "24") (name "Net-(CN2-Pad4)") (class "Default")
      (node (ref "CN2") (pin "4") (pinfunction "4_4") (pintype "unspecified"))
      (node (ref "R22") (pin "1") (pinfunction "1_1") (pintype "input"))
      (node (ref "R25") (pin "2") (pinfunction "2_2") (pintype "input"))
      (node (ref "U7") (pin "7") (pinfunction "7_7") (pintype "unspecified"))
    )
    (net (code "25") (name "Net-(D1-A)") (class "Default")
      (node (ref "D1") (pin "2") (pinfunction "A_2") (pintype "unspecified"))
      (node (ref "JP1") (pin "1") (pinfunction "1_1") (pintype "unspecified"))
      (node (ref "R7") (pin "1") (pinfunction "1_1") (pintype "input"))
    )
    (net (code "26") (name "Net-(D2-A)") (class "Default")
      (node (ref "D2") (pin "2") (pinfunction "A_2") (pintype "unspecified"))
      (node (ref "H2") (pin "7") (pinfunction "7_7") (pintype "unspecified"))
    )
    (net (code "27") (name "Net-(D4-A)") (class "Default")
      (node (ref "D4") (pin "2") (pinfunction "A_2") (pintype "unspecified"))
      (node (ref "JP1") (pin "2") (pinfunction "2_2") (pintype "unspecified"))
      (node (ref "R6") (pin "1") (pinfunction "1_1") (pintype "input"))
    )
    (net (code "28") (name "Net-(D6-C)") (class "Default")
      (node (ref "D6") (pin "1") (pinfunction "C_1") (pintype "unspecified"))
      (node (ref "D7") (pin "2") (pinfunction "A_2") (pintype "unspecified"))
    )
    (net (code "29") (name "Net-(D7-C)") (class "Default")
      (node (ref "D7") (pin "1") (pinfunction "C_1") (pintype "unspecified"))
      (node (ref "Q5") (pin "1") (pinfunction "B_1") (pintype "unspecified"))
      (node (ref "R30") (pin "2") (pinfunction "2_2") (pintype "input"))
    )
    (net (code "30") (name "Net-(D9-C)") (class "Default")
      (node (ref "D9") (pin "1") (pinfunction "C_1") (pintype "unspecified"))
      (node (ref "Q1") (pin "1") (pinfunction "B_1") (pintype "unspecified"))
      (node (ref "R4") (pin "2") (pinfunction "2_2") (pintype "input"))
    )
    (net (code "31") (name "Net-(D10-C)") (class "Default")
      (node (ref "D10") (pin "1") (pinfunction "C_1") (pintype "unspecified"))
      (node (ref "D9") (pin "2") (pinfunction "A_2") (pintype "unspecified"))
    )
    (net (code "32") (name "Net-(D11-C)") (class "Default")
      (node (ref "D11") (pin "1") (pinfunction "C_1") (pintype "unspecified"))
      (node (ref "R6") (pin "2") (pinfunction "2_2") (pintype "input"))
      (node (ref "U1") (pin "25") (pinfunction "IN2_25") (pintype "unspecified"))
    )
    (net (code "33") (name "Net-(D12-C)") (class "Default")
      (node (ref "D12") (pin "1") (pinfunction "C_1") (pintype "unspecified"))
      (node (ref "R7") (pin "2") (pinfunction "2_2") (pintype "input"))
      (node (ref "U1") (pin "27") (pinfunction "IN1_27") (pintype "unspecified"))
    )
    (net (code "34") (name "Net-(D13-A)") (class "Default")
      (node (ref "D13") (pin "2") (pinfunction "A_2") (pintype "unspecified"))
      (node (ref "Q2") (pin "1") (pinfunction "G_1") (pintype "unspecified"))
      (node (ref "R5") (pin "1") (pinfunction "1_1") (pintype "input"))
    )
    (net (code "35") (name "Net-(D14-A)") (class "Default")
      (node (ref "D14") (pin "2") (pinfunction "A_2") (pintype "unspecified"))
      (node (ref "D8") (pin "1") (pinfunction "C_1") (pintype "unspecified"))
    )
    (net (code "36") (name "Net-(D14-C)") (class "Default")
      (node (ref "D14") (pin "1") (pinfunction "C_1") (pintype "unspecified"))
      (node (ref "Q3") (pin "1") (pinfunction "B_1") (pintype "unspecified"))
      (node (ref "R8") (pin "2") (pinfunction "2_2") (pintype "input"))
    )
    (net (code "37") (name "Net-(D15-K)") (class "Default")
      (node (ref "C20") (pin "1") (pinfunction "1_1") (pintype "input"))
      (node (ref "D15") (pin "1") (pinfunction "K_1") (pintype "unspecified"))
      (node (ref "L1") (pin "1") (pinfunction "1_1") (pintype "unspecified"))
      (node (ref "U3") (pin "1") (pinfunction "SW_1") (pintype "unspecified"))
    )
    (net (code "38") (name "Net-(DCC-A)") (class "Default")
      (node (ref "DCC") (pin "1") (pinfunction "A_1") (pintype "input"))
      (node (ref "Q1") (pin "3") (pinfunction "C_3") (pintype "unspecified"))
    )
    (net (code "39") (name "Net-(DCC1-A)") (class "Default")
      (node (ref "DCC1") (pin "1") (pinfunction "A_1") (pintype "input"))
      (node (ref "Q3") (pin "3") (pinfunction "C_3") (pintype "unspecified"))
    )
    (net (code "40") (name "Net-(J2-Pad1)") (class "Default")
      (node (ref "J2") (pin "1") (pinfunction "1_1") (pintype "unspecified"))
      (node (ref "J6") (pin "3") (pinfunction "3_3") (pintype "input"))
    )
    (net (code "41") (name "Net-(J2-Pad2)") (class "Default")
      (node (ref "J2") (pin "2") (pinfunction "2_2") (pintype "unspecified"))
      (node (ref "J7") (pin "3") (pinfunction "3_3") (pintype "input"))
    )
    (net (code "42") (name "Net-(J6-Pad1)") (class "Default")
      (node (ref "J6") (pin "1") (pinfunction "1_1") (pintype "input"))
      (node (ref "J8") (pin "1") (pinfunction "1_1") (pintype "unspecified"))
    )
    (net (code "43") (name "Net-(J7-Pad1)") (class "Default")
      (node (ref "J7") (pin "1") (pinfunction "1_1") (pintype "input"))
      (node (ref "J8") (pin "2") (pinfunction "2_2") (pintype "unspecified"))
    )
    (net (code "44") (name "Net-(LED_0-DIN)") (class "Default")
      (node (ref "H2") (pin "4") (pinfunction "4_4") (pintype "unspecified"))
      (node (ref "LED_0") (pin "4") (pinfunction "DIN_4") (pintype "unspecified"))
    )
    (net (code "45") (name "Net-(LED_0-DOUT)") (class "Default")
      (node (ref "H1") (pin "2") (pinfunction "2_2") (pintype "input"))
      (node (ref "LED_0") (pin "2") (pinfunction "DOUT_2") (pintype "unspecified"))
      (node (ref "R41") (pin "1") (pinfunction "1_1") (pintype "input"))
    )
    (net (code "46") (name "Net-(Q1-E)") (class "Default")
      (node (ref "Q1") (pin "2") (pinfunction "E_2") (pintype "unspecified"))
      (node (ref "R3") (pin "1") (pinfunction "1_1") (pintype "input"))
    )
    (net (code "47") (name "Net-(Q2-D)") (class "Default")
      (node (ref "DC1") (pin "1") (pinfunction "1_1") (pintype "unspecified"))
      (node (ref "Q2") (pin "3") (pinfunction "D_3") (pintype "unspecified"))
    )
    (net (code "48") (name "Net-(Q3-E)") (class "Default")
      (node (ref "Q3") (pin "2") (pinfunction "E_2") (pintype "unspecified"))
      (node (ref "R9") (pin "1") (pinfunction "1_1") (pintype "input"))
    )
    (net (code "49") (name "Net-(Q4-B)") (class "Default")
      (node (ref "Q4") (pin "1") (pinfunction "B_1") (pintype "unspecified"))
      (node (ref "R23") (pin "1") (pinfunction "1_1") (pintype "input"))
      (node (ref "R24") (pin "2") (pinfunction "2_2") (pintype "input"))
    )
    (net (code "50") (name "Net-(Q4-C)") (class "Default")
      (node (ref "Q4") (pin "3") (pinfunction "C_3") (pintype "unspecified"))
      (node (ref "Q5") (pin "3") (pinfunction "C_3") (pintype "unspecified"))
      (node (ref "R29") (pin "1") (pinfunction "1_1") (pintype "input"))
      (node (ref "RJ11-1") (pin "3") (pinfunction "3_3") (pintype "unspecified"))
      (node (ref "RJ11-1") (pin "4") (pinfunction "4_4") (pintype "unspecified"))
      (node (ref "RJ11-2") (pin "3") (pinfunction "3_3") (pintype "unspecified"))
      (node (ref "RJ11-2") (pin "4") (pinfunction "4_4") (pintype "unspecified"))
      (node (ref "RJ11-3") (pin "3") (pinfunction "3_3") (pintype "unspecified"))
      (node (ref "RJ11-3") (pin "4") (pinfunction "4_4") (pintype "unspecified"))
    )
    (net (code "51") (name "Net-(Q5-E)") (class "Default")
      (node (ref "Q5") (pin "2") (pinfunction "E_2") (pintype "unspecified"))
      (node (ref "R31") (pin "1") (pinfunction "1_1") (pintype "input"))
    )
    (net (code "52") (name "Net-(Q6-B)") (class "Default")
      (node (ref "Q6") (pin "1") (pinfunction "B_1") (pintype "unspecified"))
      (node (ref "R19") (pin "2") (pinfunction "2_2") (pintype "input"))
      (node (ref "R20") (pin "1") (pinfunction "1_1") (pintype "input"))
    )
    (net (code "53") (name "Net-(Q6-C)") (class "Default")
      (node (ref "Q6") (pin "3") (pinfunction "C_3") (pintype "unspecified"))
      (node (ref "R21") (pin "2") (pinfunction "2_2") (pintype "input"))
      (node (ref "U1") (pin "22") (pinfunction "EN3_22") (pintype "unspecified"))
      (node (ref "U1") (pin "24") (pinfunction "EN2_24") (pintype "unspecified"))
      (node (ref "U1") (pin "26") (pinfunction "EN1_26") (pintype "unspecified"))
    )
    (net (code "54") (name "Net-(R25-Pad1)") (class "Default")
      (node (ref "R25") (pin "1") (pinfunction "1_1") (pintype "input"))
      (node (ref "R26") (pin "1") (pinfunction "1_1") (pintype "input"))
      (node (ref "R27") (pin "2") (pinfunction "2_2") (pintype "input"))
      (node (ref "U7") (pin "2") (pinfunction "2_2") (pintype "unspecified"))
    )
    (net (code "55") (name "Net-(R28-Pad1)") (class "Default")
      (node (ref "R28") (pin "1") (pinfunction "1_1") (pintype "input"))
      (node (ref "R29") (pin "2") (pinfunction "2_2") (pintype "input"))
      (node (ref "U7") (pin "3") (pinfunction "3_3") (pintype "unspecified"))
    )
    (net (code "56") (name "Net-(U1-COMPN)") (class "Default")
      (node (ref "R16") (pin "2") (pinfunction "2_2") (pintype "input"))
      (node (ref "R17") (pin "1") (pinfunction "1_1") (pintype "input"))
      (node (ref "U1") (pin "13") (pinfunction "COMPN_13") (pintype "unspecified"))
    )
    (net (code "57") (name "Net-(U1-COMPO#)") (class "Default")
      (node (ref "R14") (pin "1") (pinfunction "1_1") (pintype "input"))
      (node (ref "R15") (pin "2") (pinfunction "2_2") (pintype "input"))
      (node (ref "U1") (pin "19") (pinfunction "COMPO#_19") (pintype "unspecified"))
    )
    (net (code "58") (name "Net-(U1-COMPP)") (class "Default")
      (node (ref "R18") (pin "2") (pinfunction "2_2") (pintype "input"))
      (node (ref "U1") (pin "10") (pinfunction "PGND3_10") (pintype "unspecified"))
      (node (ref "U1") (pin "12") (pinfunction "COMPP_12") (pintype "unspecified"))
      (node (ref "U1") (pin "6") (pinfunction "PGND1_6") (pintype "unspecified"))
      (node (ref "U1") (pin "7") (pinfunction "PGND2_7") (pintype "unspecified"))
    )
    (net (code "59") (name "Net-(U1-CP1)") (class "Default")
      (node (ref "C10") (pin "2") (pinfunction "2_2") (pintype "unspecified"))
      (node (ref "U1") (pin "1") (pinfunction "CP1_1") (pintype "unspecified"))
    )
    (net (code "60") (name "Net-(U1-CP2)") (class "Default")
      (node (ref "C10") (pin "1") (pinfunction "1_1") (pintype "unspecified"))
      (node (ref "U1") (pin "2") (pinfunction "CP2_2") (pintype "unspecified"))
    )
    (net (code "61") (name "Net-(U1-OUT1)") (class "Default")
      (node (ref "RJ11-3") (pin "6") (pinfunction "6_6") (pintype "unspecified"))
      (node (ref "U1") (pin "5") (pinfunction "OUT1_5") (pintype "unspecified"))
    )
    (net (code "62") (name "Net-(U1-OUT2)") (class "Default")
      (node (ref "RJ11-3") (pin "1") (pinfunction "1_1") (pintype "unspecified"))
      (node (ref "U1") (pin "8") (pinfunction "OUT2_8") (pintype "unspecified"))
    )
    (net (code "63") (name "Net-(U1-OUT3)") (class "Default")
      (node (ref "RJ11-1") (pin "1") (pinfunction "1_1") (pintype "unspecified"))
      (node (ref "RJ11-1") (pin "6") (pinfunction "6_6") (pintype "unspecified"))
      (node (ref "RJ11-2") (pin "1") (pinfunction "1_1") (pintype "unspecified"))
      (node (ref "RJ11-2") (pin "6") (pinfunction "6_6") (pintype "unspecified"))
      (node (ref "U1") (pin "9") (pinfunction "OUT3_9") (pintype "unspecified"))
    )
    (net (code "64") (name "Net-(U1-V3P3OUT)") (class "Default")
      (node (ref "C11") (pin "1") (pinfunction "1_1") (pintype "input"))
      (node (ref "R17") (pin "2") (pinfunction "2_2") (pintype "input"))
      (node (ref "U1") (pin "15") (pinfunction "V3P3OUT_15") (pintype "unspecified"))
    )
    (net (code "65") (name "Net-(U1-VCP)") (class "Default")
      (node (ref "C7") (pin "2") (pinfunction "2_2") (pintype "unspecified"))
      (node (ref "U1") (pin "3") (pinfunction "VCP_3") (pintype "unspecified"))
    )
    (net (code "66") (name "Net-(U3-BST)") (class "Default")
      (node (ref "C20") (pin "2") (pinfunction "2_2") (pintype "input"))
      (node (ref "U3") (pin "8") (pinfunction "BST_8") (pintype "unspecified"))
    )
    (net (code "67") (name "Net-(U3-COMP)") (class "Default")
      (node (ref "R13") (pin "2") (pinfunction "2_2") (pintype "input"))
      (node (ref "U3") (pin "3") (pinfunction "COMP_3") (pintype "unspecified"))
    )
    (net (code "68") (name "Net-(U3-FB)") (class "Default")
      (node (ref "R10") (pin "1") (pinfunction "1_1") (pintype "input"))
      (node (ref "R11") (pin "2") (pinfunction "2_2") (pintype "input"))
      (node (ref "U3") (pin "4") (pinfunction "FB_4") (pintype "unspecified"))
    )
    (net (code "69") (name "Net-(U3-FREQ)") (class "Default")
      (node (ref "R12") (pin "1") (pinfunction "1_1") (pintype "input"))
      (node (ref "U3") (pin "6") (pinfunction "FREQ_6") (pintype "unspecified"))
    )
    (net (code "70") (name "Net-(U4-A)") (class "Default")
      (node (ref "C14") (pin "2") (pinfunction "2_2") (pintype "input"))
      (node (ref "R14") (pin "2") (pinfunction "2_2") (pintype "input"))
      (node (ref "U4") (pin "2") (pinfunction "A_2") (pintype "unspecified"))
    )
    (net (code "71") (name "Net-(U4-Y)") (class "Default")
      (node (ref "R19") (pin "1") (pinfunction "1_1") (pintype "input"))
      (node (ref "U4") (pin "4") (pinfunction "Y_4") (pintype "unspecified"))
    )
    (net (code "72") (name "Reset") (class "Default")
      (node (ref "J3") (pin "6") (pinfunction "6_6") (pintype "unspecified"))
    )
    (net (code "73") (name "RxD") (class "Default")
      (node (ref "J5") (pin "1") (pinfunction "1_1") (pintype "unspecified"))
      (node (ref "J7") (pin "2") (pinfunction "2_2") (pintype "input"))
      (node (ref "R1") (pin "2") (pinfunction "2_2") (pintype "input"))
    )
    (net (code "74") (name "RxD-33") (class "Default")
      (node (ref "H2") (pin "5") (pinfunction "5_5") (pintype "unspecified"))
      (node (ref "J5") (pin "2") (pinfunction "2_2") (pintype "unspecified"))
      (node (ref "R1") (pin "1") (pinfunction "1_1") (pintype "input"))
      (node (ref "R2") (pin "2") (pinfunction "2_2") (pintype "input"))
    )
    (net (code "75") (name "TxD") (class "Default")
      (node (ref "H2") (pin "6") (pinfunction "6_6") (pintype "unspecified"))
      (node (ref "J6") (pin "2") (pinfunction "2_2") (pintype "input"))
    )
    (net (code "76") (name "VCC3.3") (class "Default")
      (node (ref "C3") (pin "2") (pinfunction "2_2") (pintype "unspecified"))
      (node (ref "C5") (pin "2") (pinfunction "2_2") (pintype "unspecified"))
      (node (ref "C8") (pin "2") (pinfunction "2_2") (pintype "unspecified"))
      (node (ref "C9") (pin "2") (pinfunction "2_2") (pintype "unspecified"))
      (node (ref "D3") (pin "2") (pinfunction "A_2") (pintype "unspecified"))
      (node (ref "H2") (pin "2") (pinfunction "2_2") (pintype "unspecified"))
      (node (ref "LED_0") (pin "1") (pinfunction "VDD_1") (pintype "unspecified"))
      (node (ref "R22") (pin "2") (pinfunction "2_2") (pintype "input"))
      (node (ref "R27") (pin "1") (pinfunction "1_1") (pintype "input"))
      (node (ref "U7") (pin "8") (pinfunction "VCC_8") (pintype "unspecified"))
    )
    (net (code "77") (name "VCC15.0") (class "Default")
      (node (ref "C16") (pin "2") (pinfunction "2_2") (pintype "unspecified"))
      (node (ref "C17") (pin "2") (pinfunction "2_2") (pintype "unspecified"))
      (node (ref "C7") (pin "1") (pinfunction "1_1") (pintype "unspecified"))
      (node (ref "D10") (pin "2") (pinfunction "A_2") (pintype "unspecified"))
      (node (ref "R3") (pin "2") (pinfunction "2_2") (pintype "input"))
      (node (ref "U1") (pin "11") (pinfunction "VM_11") (pintype "unspecified"))
      (node (ref "U1") (pin "4") (pinfunction "VM_4") (pintype "unspecified"))
      (node (ref "U2") (pin "3") (pinfunction "OUT_3") (pintype "unspecified"))
    )
    (net (code "78") (name "VDCC+") (class "Default")
      (node (ref "C6") (pin "2") (pinfunction "2_2") (pintype "unspecified"))
      (node (ref "D1") (pin "1") (pinfunction "C_1") (pintype "unspecified"))
      (node (ref "D4") (pin "1") (pinfunction "C_1") (pintype "unspecified"))
      (node (ref "D5") (pin "1") (pinfunction "C_1") (pintype "unspecified"))
      (node (ref "U2") (pin "1") (pinfunction "IN_1") (pintype "unspecified"))
    )
    (net (code "79") (name "VIN") (class "Default")
      (node (ref "C12") (pin "2") (pinfunction "2_2") (pintype "input"))
      (node (ref "C13") (pin "1") (pinfunction "1_1") (pintype "input"))
      (node (ref "C15") (pin "2") (pinfunction "2_2") (pintype "input"))
      (node (ref "D13") (pin "1") (pinfunction "K_1") (pintype "unspecified"))
      (node (ref "D5") (pin "2") (pinfunction "A_2") (pintype "unspecified"))
      (node (ref "D6") (pin "2") (pinfunction "A_2") (pintype "unspecified"))
      (node (ref "D8") (pin "2") (pinfunction "A_2") (pintype "unspecified"))
      (node (ref "J3") (pin "1") (pinfunction "1_1") (pintype "unspecified"))
      (node (ref "Q2") (pin "2") (pinfunction "S_2") (pintype "unspecified"))
      (node (ref "R31") (pin "2") (pinfunction "2_2") (pintype "input"))
      (node (ref "R9") (pin "2") (pinfunction "2_2") (pintype "input"))
      (node (ref "U3") (pin "7") (pinfunction "VIN_7") (pintype "unspecified"))
    )
    (net (code "80") (name "unconnected-(CN2-Pad2)") (class "Default")
      (node (ref "CN2") (pin "2") (pinfunction "2_2") (pintype "unspecified"))
    )
    (net (code "81") (name "unconnected-(H2-Pad3)") (class "Default")
      (node (ref "H2") (pin "3") (pinfunction "3_3") (pintype "unspecified"))
    )
    (net (code "82") (name "unconnected-(J3-Pad8)") (class "Default")
      (node (ref "J3") (pin "8") (pinfunction "8_8") (pintype "unspecified"))
    )
    (net (code "83") (name "unconnected-(J4-Pad8)") (class "Default")
      (node (ref "J4") (pin "8") (pinfunction "8_8") (pintype "unspecified"))
    )
    (net (code "84") (name "unconnected-(J4-Pad9)") (class "Default")
      (node (ref "J4") (pin "9") (pinfunction "9_9") (pintype "unspecified"))
    )
    (net (code "85") (name "unconnected-(J4-Pad10)") (class "Default")
      (node (ref "J4") (pin "10") (pinfunction "10_10") (pintype "unspecified"))
    )
    (net (code "86") (name "unconnected-(U1-FAULT#-Pad18)") (class "Default")
      (node (ref "U1") (pin "18") (pinfunction "FAULT#_18") (pintype "unspecified"))
    )
    (net (code "87") (name "unconnected-(U1-NC-Pad21)") (class "Default")
      (node (ref "U1") (pin "21") (pinfunction "NC_21") (pintype "unspecified"))
    )
    (net (code "88") (name "unconnected-(U3-EN-Pad2)") (class "Default")
      (node (ref "U3") (pin "2") (pinfunction "EN_2") (pintype "unspecified+no_connect"))
    )
    (net (code "89") (name "unconnected-(U4-N.C-Pad1)") (class "Default")
      (node (ref "U4") (pin "1") (pinfunction "N.C_1") (pintype "unspecified"))
    )
    (net (code "90") (name "unconnected-(U7-BALANCE-Pad5)") (class "Default")
      (node (ref "U7") (pin "5") (pinfunction "BALANCE_5") (pintype "unspecified"))
    )
    (net (code "91") (name "unconnected-(U7-BALANCE{slash}STROBE-Pad6)") (class "Default")
      (node (ref "U7") (pin "6") (pinfunction "BALANCE/STROBE_6") (pintype "unspecified"))
    )
  )
)
